# can-5-way.net
KiCad netlist of a schematic drawn in EAGLE
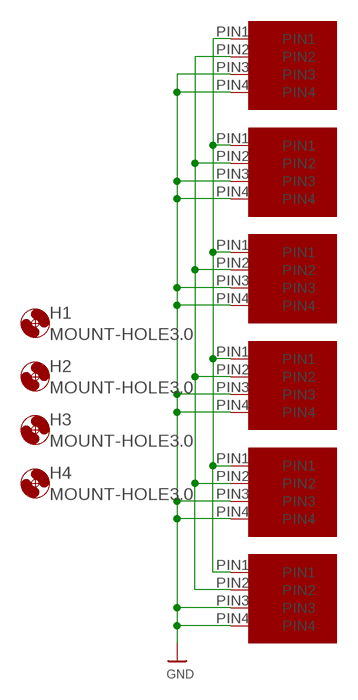
[diagram p0: schematic, sheet 1]

(export (version "E")
  (design (tool "Eeschema 10.0.6"))
  (components
    (comp (ref "H1")
      (value "MOUNT-HOLE3.0")
      (footprint "eagle-import:3,0")
      (libsource (lib "eagle-import") (part "MOUNT-HOLE3.0"))
    )
    (comp (ref "H2")
      (value "MOUNT-HOLE3.0")
      (footprint "eagle-import:3,0")
      (libsource (lib "eagle-import") (part "MOUNT-HOLE3.0"))
    )
    (comp (ref "H3")
      (value "MOUNT-HOLE3.0")
      (footprint "eagle-import:3,0")
      (libsource (lib "eagle-import") (part "MOUNT-HOLE3.0"))
    )
    (comp (ref "H4")
      (value "MOUNT-HOLE3.0")
      (footprint "eagle-import:3,0")
      (libsource (lib "eagle-import") (part "MOUNT-HOLE3.0"))
    )
    (comp (ref "U$1")
      (value "MICROFIT4")
      (footprint "eagle-import:MICROFIT4SOCK")
      (libsource (lib "eagle-import") (part "MICROFIT4"))
    )
    (comp (ref "U$2")
      (value "MICROFIT4")
      (footprint "eagle-import:MICROFIT4SOCK")
      (libsource (lib "eagle-import") (part "MICROFIT4"))
    )
    (comp (ref "U$3")
      (value "MICROFIT4")
      (footprint "eagle-import:MICROFIT4SOCK")
      (libsource (lib "eagle-import") (part "MICROFIT4"))
    )
    (comp (ref "U$4")
      (value "MICROFIT4")
      (footprint "eagle-import:MICROFIT4SOCK")
      (libsource (lib "eagle-import") (part "MICROFIT4"))
    )
    (comp (ref "U$5")
      (value "MICROFIT4")
      (footprint "eagle-import:MICROFIT4SOCK")
      (libsource (lib "eagle-import") (part "MICROFIT4"))
    )
    (comp (ref "U$7")
      (value "MICROFIT4")
      (footprint "eagle-import:MICROFIT4SOCK")
      (libsource (lib "eagle-import") (part "MICROFIT4"))
    )
  )
  (nets
    (net (code "1") (name "GND") (class "Default")
      (node (ref "U$1") (pin "PIN3") (pinfunction "PIN3_PIN3") (pintype "bidirectional"))
      (node (ref "U$1") (pin "PIN4") (pinfunction "PIN4_PIN4") (pintype "bidirectional"))
      (node (ref "U$2") (pin "PIN3") (pinfunction "PIN3_PIN3") (pintype "bidirectional"))
      (node (ref "U$2") (pin "PIN4") (pinfunction "PIN4_PIN4") (pintype "bidirectional"))
      (node (ref "U$3") (pin "PIN3") (pinfunction "PIN3_PIN3") (pintype "bidirectional"))
      (node (ref "U$3") (pin "PIN4") (pinfunction "PIN4_PIN4") (pintype "bidirectional"))
      (node (ref "U$4") (pin "PIN3") (pinfunction "PIN3_PIN3") (pintype "bidirectional"))
      (node (ref "U$4") (pin "PIN4") (pinfunction "PIN4_PIN4") (pintype "bidirectional"))
      (node (ref "U$5") (pin "PIN3") (pinfunction "PIN3_PIN3") (pintype "bidirectional"))
      (node (ref "U$5") (pin "PIN4") (pinfunction "PIN4_PIN4") (pintype "bidirectional"))
      (node (ref "U$7") (pin "PIN3") (pinfunction "PIN3_PIN3") (pintype "bidirectional"))
      (node (ref "U$7") (pin "PIN4") (pinfunction "PIN4_PIN4") (pintype "bidirectional"))
    )
    (net (code "2") (name "Net-(U$1-PadPIN1)") (class "Default")
      (node (ref "U$1") (pin "PIN1") (pinfunction "PIN1_PIN1") (pintype "bidirectional"))
      (node (ref "U$2") (pin "PIN1") (pinfunction "PIN1_PIN1") (pintype "bidirectional"))
      (node (ref "U$3") (pin "PIN1") (pinfunction "PIN1_PIN1") (pintype "bidirectional"))
      (node (ref "U$4") (pin "PIN1") (pinfunction "PIN1_PIN1") (pintype "bidirectional"))
      (node (ref "U$5") (pin "PIN1") (pinfunction "PIN1_PIN1") (pintype "bidirectional"))
      (node (ref "U$7") (pin "PIN1") (pinfunction "PIN1_PIN1") (pintype "bidirectional"))
    )
    (net (code "3") (name "Net-(U$1-PadPIN2)") (class "Default")
      (node (ref "U$1") (pin "PIN2") (pinfunction "PIN2_PIN2") (pintype "bidirectional"))
      (node (ref "U$2") (pin "PIN2") (pinfunction "PIN2_PIN2") (pintype "bidirectional"))
      (node (ref "U$3") (pin "PIN2") (pinfunction "PIN2_PIN2") (pintype "bidirectional"))
      (node (ref "U$4") (pin "PIN2") (pinfunction "PIN2_PIN2") (pintype "bidirectional"))
      (node (ref "U$5") (pin "PIN2") (pinfunction "PIN2_PIN2") (pintype "bidirectional"))
      (node (ref "U$7") (pin "PIN2") (pinfunction "PIN2_PIN2") (pintype "bidirectional"))
    )
  )
)
